# Fan.net
KiCad netlist of a schematic drawn in EAGLE
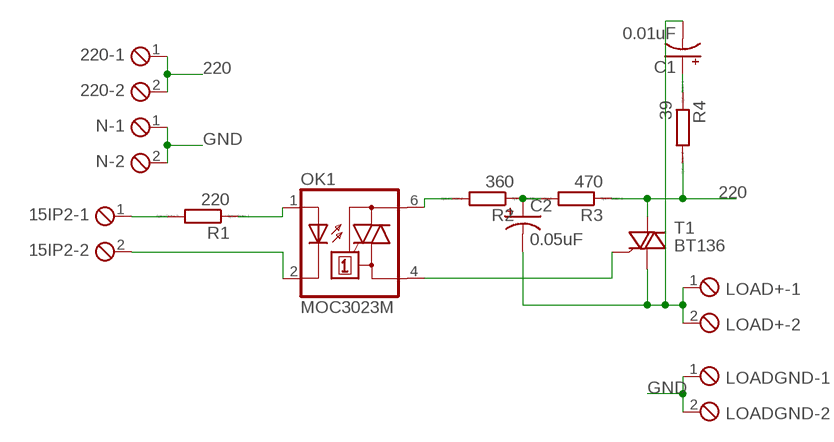
[diagram p0: schematic, sheet 1]

(export (version "E")
  (design (tool "Eeschema 10.0.6"))
  (components
    (comp (ref "15IP2")
      (value "MPT2")
      (footprint "eagle-import:2POL254")
      (libsource (lib "eagle-import") (part "MPT2"))
    )
    (comp (ref "220")
      (value "MPT2")
      (footprint "eagle-import:2POL254")
      (libsource (lib "eagle-import") (part "MPT2"))
    )
    (comp (ref "C1")
      (value "0.01uF")
      (footprint "eagle-import:CPOL-RADIAL-5MM-10MM")
      (libsource (lib "eagle-import") (part "1000UF-RADIAL-5MM-25V-20%"))
    )
    (comp (ref "C2")
      (value "0.05uF")
      (footprint "eagle-import:CPOL-RADIAL-5MM-10MM")
      (libsource (lib "eagle-import") (part "1000UF-RADIAL-5MM-25V-20%"))
    )
    (comp (ref "LOAD+")
      (value "MPT2")
      (footprint "eagle-import:2POL254")
      (libsource (lib "eagle-import") (part "MPT2"))
    )
    (comp (ref "LOADGND")
      (value "MPT2")
      (footprint "eagle-import:2POL254")
      (libsource (lib "eagle-import") (part "MPT2"))
    )
    (comp (ref "N")
      (value "MPT2")
      (footprint "eagle-import:2POL254")
      (libsource (lib "eagle-import") (part "MPT2"))
    )
    (comp (ref "OK1")
      (value "MOC3023M")
      (footprint "eagle-import:DIL06")
      (fields (field (name "MF") "FAIRCHILD SEMICONDUCTOR") (field (name "MPN") "MOC3023-M"))
      (libsource (lib "eagle-import") (part "MOC30M23"))
    )
    (comp (ref "R1")
      (value "220")
      (footprint "eagle-import:0204_7")
      (libsource (lib "eagle-import") (part "R0204/7"))
    )
    (comp (ref "R2")
      (value "360")
      (footprint "eagle-import:0204_7")
      (libsource (lib "eagle-import") (part "R0204/7"))
    )
    (comp (ref "R3")
      (value "470")
      (footprint "eagle-import:0204_7")
      (libsource (lib "eagle-import") (part "R0204/7"))
    )
    (comp (ref "R4")
      (value "39")
      (footprint "eagle-import:0204_7")
      (libsource (lib "eagle-import") (part "R0204/7"))
    )
    (comp (ref "T1")
      (value "BT136")
      (footprint "eagle-import:TO220AB")
      (libsource (lib "eagle-import") (part "BT136"))
    )
  )
  (nets
    (net (code "1") (name "/220") (class "Default")
      (node (ref "220") (pin "1") (pinfunction "1_1") (pintype "passive"))
      (node (ref "220") (pin "2") (pinfunction "1_2") (pintype "passive"))
      (node (ref "R3") (pin "1") (pinfunction "1_1") (pintype "passive"))
      (node (ref "R4") (pin "2") (pinfunction "2_2") (pintype "passive"))
      (node (ref "T1") (pin "2") (pinfunction "A2_2") (pintype "passive"))
    )
    (net (code "2") (name "/GND") (class "Default")
      (node (ref "LOADGND") (pin "1") (pinfunction "1_1") (pintype "passive"))
      (node (ref "LOADGND") (pin "2") (pinfunction "1_2") (pintype "passive"))
      (node (ref "N") (pin "1") (pinfunction "1_1") (pintype "passive"))
      (node (ref "N") (pin "2") (pinfunction "1_2") (pintype "passive"))
    )
    (net (code "3") (name "Net-(15IP2-Pad1)") (class "Default")
      (node (ref "15IP2") (pin "1") (pinfunction "1_1") (pintype "passive"))
      (node (ref "R1") (pin "2") (pinfunction "2_2") (pintype "passive"))
    )
    (net (code "4") (name "Net-(15IP2B-1)") (class "Default")
      (node (ref "15IP2") (pin "2") (pinfunction "1_2") (pintype "passive"))
      (node (ref "OK1") (pin "2") (pinfunction "C_2") (pintype "passive"))
    )
    (net (code "5") (name "Net-(C1-Pad+)") (class "Default")
      (node (ref "C1") (pin "+") (pinfunction "+_+") (pintype "passive"))
      (node (ref "R4") (pin "1") (pinfunction "1_1") (pintype "passive"))
    )
    (net (code "6") (name "Net-(C2-Pad+)") (class "Default")
      (node (ref "C2") (pin "+") (pinfunction "+_+") (pintype "passive"))
      (node (ref "R2") (pin "1") (pinfunction "1_1") (pintype "passive"))
      (node (ref "R3") (pin "2") (pinfunction "2_2") (pintype "passive"))
    )
    (net (code "7") (name "Net-(LOAD+B-1)") (class "Default")
      (node (ref "C1") (pin "-") (pinfunction "-_-") (pintype "passive"))
      (node (ref "C2") (pin "-") (pinfunction "-_-") (pintype "passive"))
      (node (ref "LOAD+") (pin "1") (pinfunction "1_1") (pintype "passive"))
      (node (ref "LOAD+") (pin "2") (pinfunction "1_2") (pintype "passive"))
      (node (ref "T1") (pin "1") (pinfunction "A1_1") (pintype "passive"))
    )
    (net (code "8") (name "Net-(OK1-A)") (class "Default")
      (node (ref "OK1") (pin "1") (pinfunction "A_1") (pintype "passive"))
      (node (ref "R1") (pin "1") (pinfunction "1_1") (pintype "passive"))
    )
    (net (code "9") (name "Net-(OK1-A1)") (class "Default")
      (node (ref "OK1") (pin "4") (pinfunction "A1_4") (pintype "passive"))
      (node (ref "T1") (pin "3") (pinfunction "G_3") (pintype "passive"))
    )
    (net (code "10") (name "Net-(OK1-A2)") (class "Default")
      (node (ref "OK1") (pin "6") (pinfunction "A2_6") (pintype "passive"))
      (node (ref "R2") (pin "2") (pinfunction "2_2") (pintype "passive"))
    )
  )
)
